# uart_opto_isolation.net
KiCad netlist of a schematic drawn in EAGLE
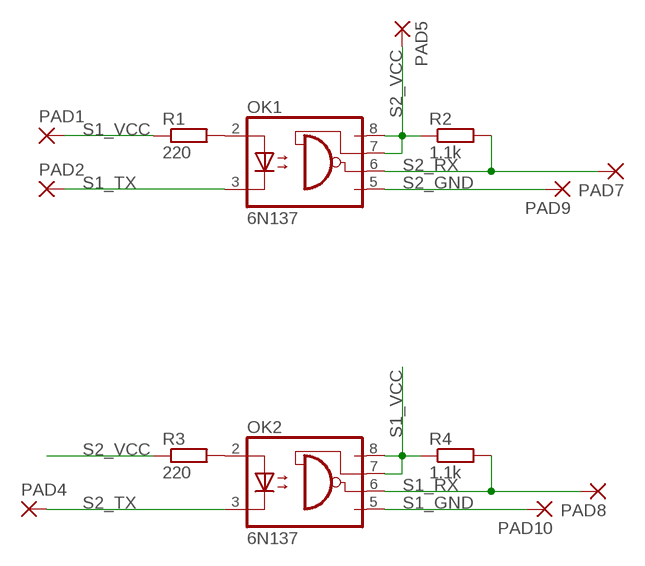
[diagram p0: schematic, sheet 1]

(export (version "E")
  (design (tool "Eeschema 10.0.6"))
  (components
    (comp (ref "OK1")
      (value "6N137")
      (footprint "eagle-import:DIL08")
      (libsource (lib "eagle-import") (part "6N137"))
    )
    (comp (ref "OK2")
      (value "6N137")
      (footprint "eagle-import:DIL08")
      (fields
        (field (name "MPN") "6N137")
        (field (name "OC_FARNELL") "1328376")
        (field (name "OC_NEWARK") "52M1895")
      )
      (libsource (lib "eagle-import") (part "6N137"))
    )
    (comp (ref "PAD1")
      (value "1,6/0,9")
      (footprint "eagle-import:1,6_0,9")
      (libsource (lib "eagle-import") (part "1,6/0,9"))
    )
    (comp (ref "PAD2")
      (value "1,6/0,9")
      (footprint "eagle-import:1,6_0,9")
      (libsource (lib "eagle-import") (part "1,6/0,9"))
    )
    (comp (ref "PAD4")
      (value "1,6/0,9")
      (footprint "eagle-import:1,6_0,9")
      (libsource (lib "eagle-import") (part "1,6/0,9"))
    )
    (comp (ref "PAD5")
      (value "1,6/0,9")
      (footprint "eagle-import:1,6_0,9")
      (libsource (lib "eagle-import") (part "1,6/0,9"))
    )
    (comp (ref "PAD7")
      (value "1,6/0,9")
      (footprint "eagle-import:1,6_0,9")
      (libsource (lib "eagle-import") (part "1,6/0,9"))
    )
    (comp (ref "PAD8")
      (value "1,6/0,9")
      (footprint "eagle-import:1,6_0,9")
      (libsource (lib "eagle-import") (part "1,6/0,9"))
    )
    (comp (ref "PAD9")
      (value "1,6/0,9")
      (footprint "eagle-import:1,6_0,9")
      (libsource (lib "eagle-import") (part "1,6/0,9"))
    )
    (comp (ref "PAD10")
      (value "1,6/0,9")
      (footprint "eagle-import:1,6_0,9")
      (libsource (lib "eagle-import") (part "1,6/0,9"))
    )
    (comp (ref "R1")
      (value "220")
      (footprint "eagle-import:R0805")
      (libsource (lib "eagle-import") (part "R-EU_R0805"))
    )
    (comp (ref "R2")
      (value "1.1k")
      (footprint "eagle-import:R0805")
      (libsource (lib "eagle-import") (part "R-EU_R0805"))
    )
    (comp (ref "R3")
      (value "220")
      (footprint "eagle-import:R0805")
      (libsource (lib "eagle-import") (part "R-EU_R0805"))
    )
    (comp (ref "R4")
      (value "1.1k")
      (footprint "eagle-import:R0805")
      (libsource (lib "eagle-import") (part "R-EU_R0805"))
    )
  )
  (nets
    (net (code "1") (name "/S1_GND") (class "Default")
      (node (ref "OK2") (pin "5") (pinfunction "GND_5") (pintype "passive"))
      (node (ref "PAD10") (pin "1") (pinfunction "P_1") (pintype "passive"))
    )
    (net (code "2") (name "/S1_RX") (class "Default")
      (node (ref "OK2") (pin "6") (pinfunction "VO_6") (pintype "passive"))
      (node (ref "PAD8") (pin "1") (pinfunction "P_1") (pintype "passive"))
      (node (ref "R4") (pin "2") (pinfunction "2_2") (pintype "passive"))
    )
    (net (code "3") (name "/S1_TX") (class "Default")
      (node (ref "OK1") (pin "3") (pinfunction "C_3") (pintype "passive"))
      (node (ref "PAD2") (pin "1") (pinfunction "P_1") (pintype "passive"))
    )
    (net (code "4") (name "/S1_VCC") (class "Default")
      (node (ref "OK2") (pin "7") (pinfunction "VE_7") (pintype "passive"))
      (node (ref "OK2") (pin "8") (pinfunction "VCC_8") (pintype "passive"))
      (node (ref "PAD1") (pin "1") (pinfunction "P_1") (pintype "passive"))
      (node (ref "R1") (pin "1") (pinfunction "1_1") (pintype "passive"))
      (node (ref "R4") (pin "1") (pinfunction "1_1") (pintype "passive"))
    )
    (net (code "5") (name "/S2_GND") (class "Default")
      (node (ref "OK1") (pin "5") (pinfunction "GND_5") (pintype "passive"))
      (node (ref "PAD9") (pin "1") (pinfunction "P_1") (pintype "passive"))
    )
    (net (code "6") (name "/S2_RX") (class "Default")
      (node (ref "OK1") (pin "6") (pinfunction "VO_6") (pintype "passive"))
      (node (ref "PAD7") (pin "1") (pinfunction "P_1") (pintype "passive"))
      (node (ref "R2") (pin "2") (pinfunction "2_2") (pintype "passive"))
    )
    (net (code "7") (name "/S2_TX") (class "Default")
      (node (ref "OK2") (pin "3") (pinfunction "C_3") (pintype "passive"))
      (node (ref "PAD4") (pin "1") (pinfunction "P_1") (pintype "passive"))
    )
    (net (code "8") (name "/S2_VCC") (class "Default")
      (node (ref "OK1") (pin "7") (pinfunction "VE_7") (pintype "passive"))
      (node (ref "OK1") (pin "8") (pinfunction "VCC_8") (pintype "passive"))
      (node (ref "PAD5") (pin "1") (pinfunction "P_1") (pintype "passive"))
      (node (ref "R2") (pin "1") (pinfunction "1_1") (pintype "passive"))
      (node (ref "R3") (pin "1") (pinfunction "1_1") (pintype "passive"))
    )
    (net (code "9") (name "Net-(OK1-A)") (class "Default")
      (node (ref "OK1") (pin "2") (pinfunction "A_2") (pintype "passive"))
      (node (ref "R1") (pin "2") (pinfunction "2_2") (pintype "passive"))
    )
    (net (code "10") (name "Net-(OK2-A)") (class "Default")
      (node (ref "OK2") (pin "2") (pinfunction "A_2") (pintype "passive"))
      (node (ref "R3") (pin "2") (pinfunction "2_2") (pintype "passive"))
    )
  )
)
